# K-Line.net
KiCad netlist of a schematic drawn in Altium Designer
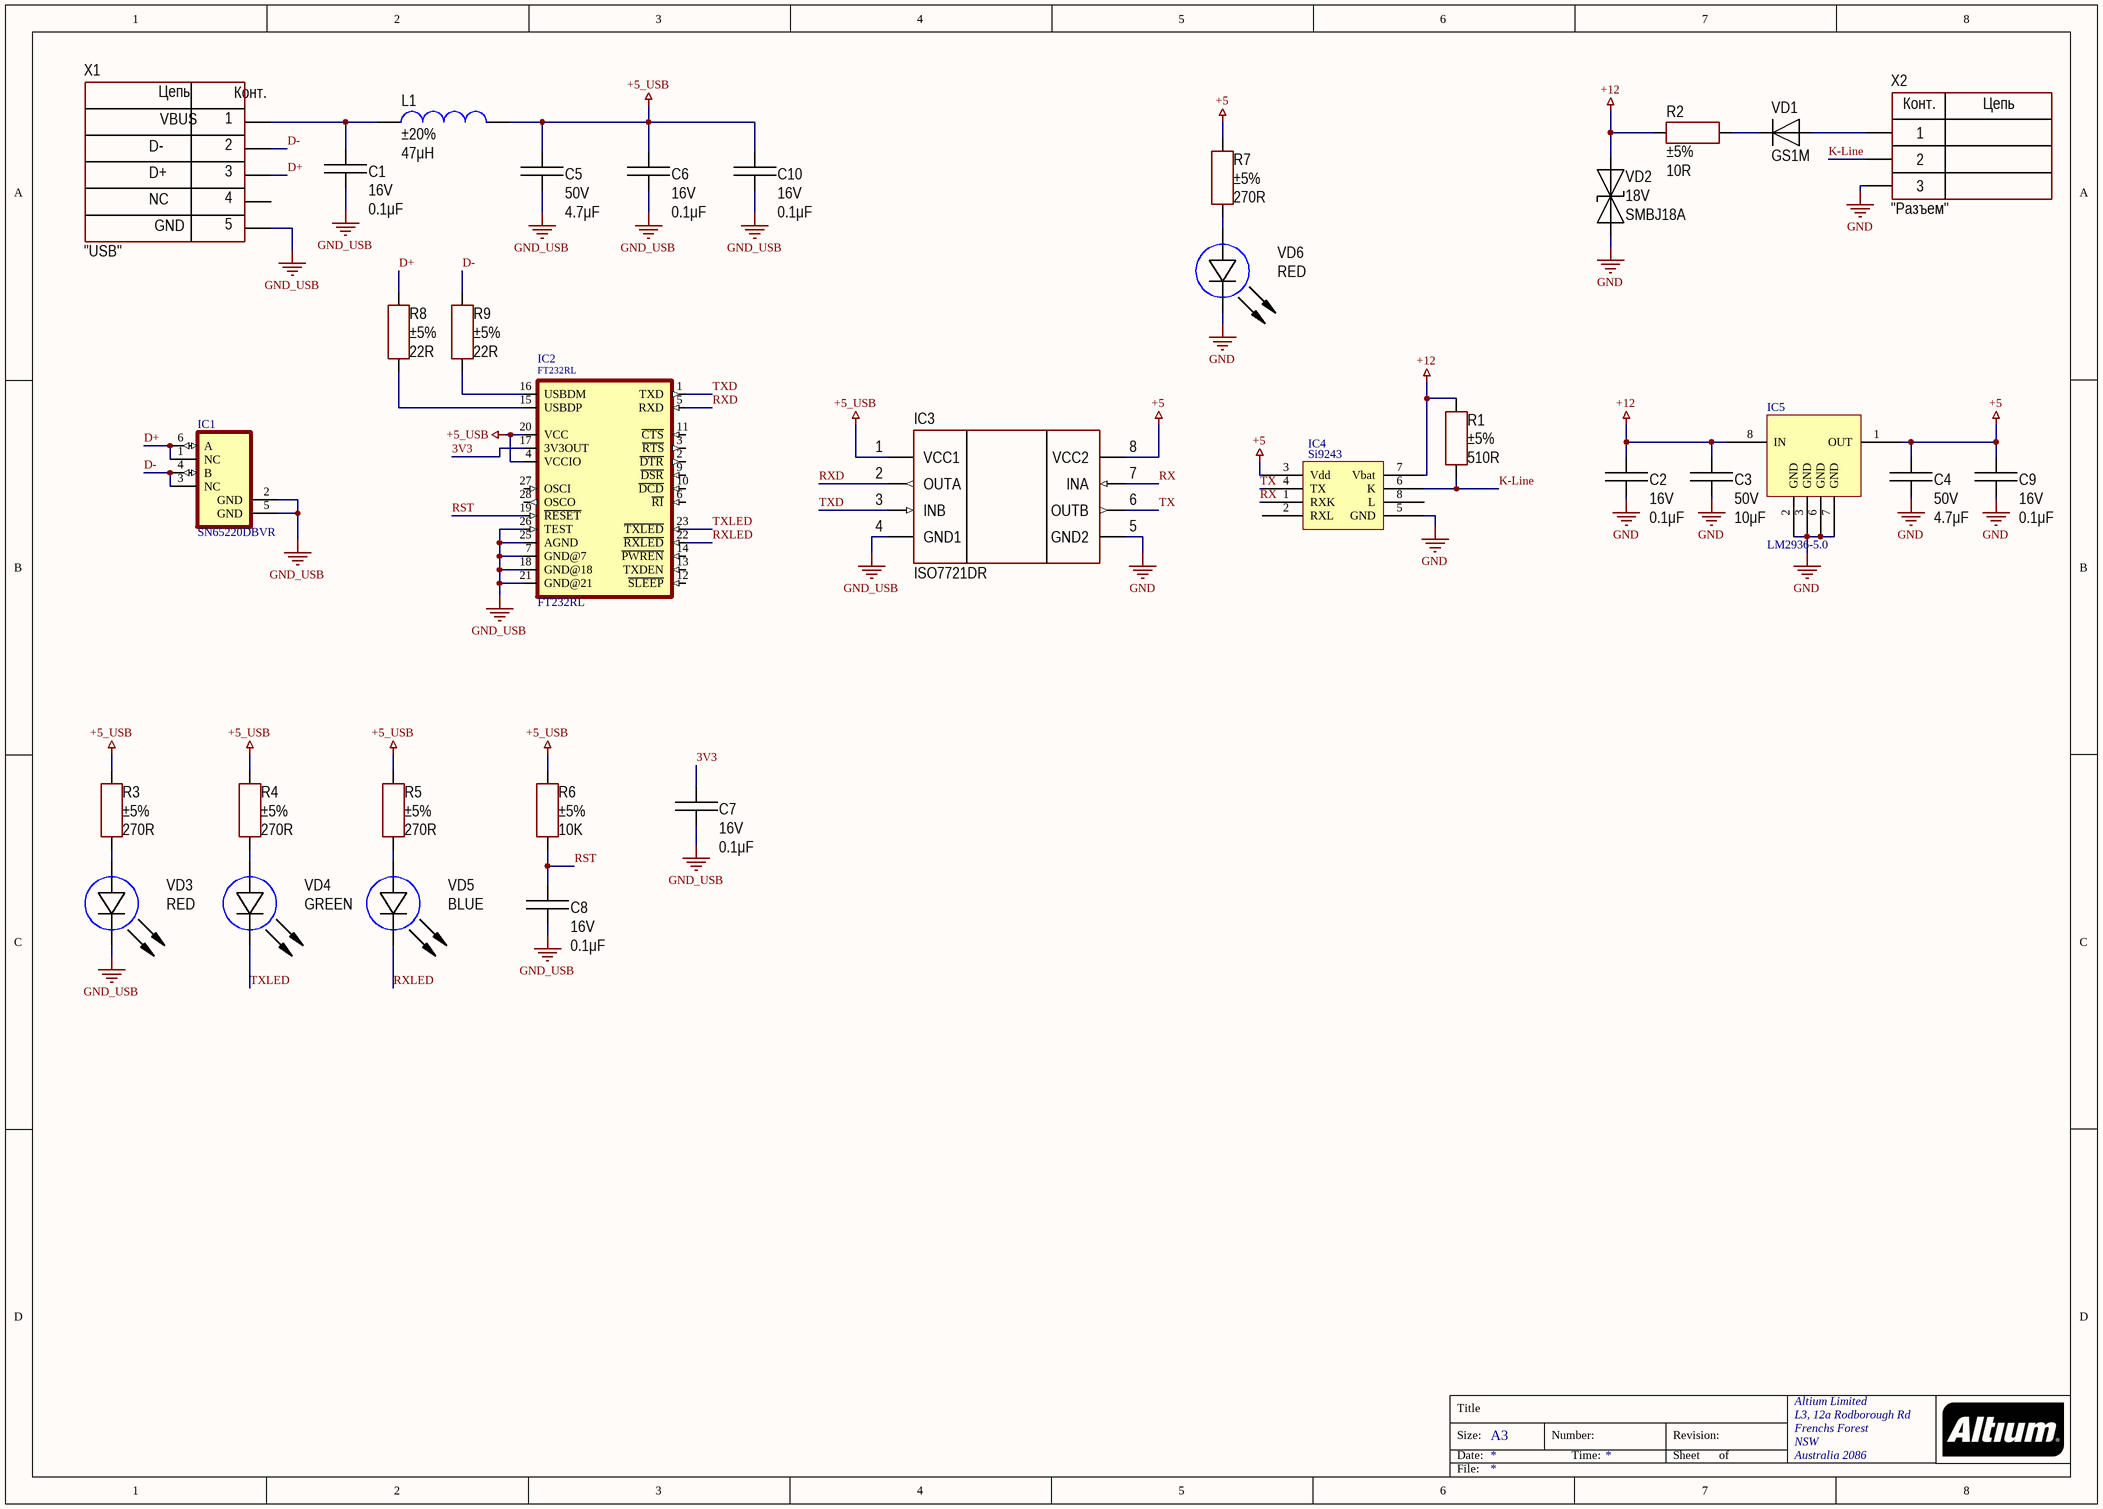
[diagram p0: K-Line.SchDoc]

(export (version "E")
  (design (tool "Eeschema 10.0.6"))
  (components
    (comp (ref "C1")
      (value "0.1μF")
      (footprint "StandardCase:CAP: 0805")
      (fields
        (field (name "MANUFACTURER") "Yageo")
        (field (name "PARTNUMBER") "CC0805KRX7R7BB104")
        (field (name "VALUEMANUFACTURERPARTNUMBER") "Ceramic capacitor, 0.1μF, X7R, ±10%, 16V, 0805, -55...+125°C")
        (field (name "VOLTAGE") "16V")
      )
      (libsource (lib "Capacitor") (part "Ceramic_0805"))
    )
    (comp (ref "C2")
      (value "0.1μF")
      (footprint "StandardCase:CAP: 0805")
      (fields
        (field (name "MANUFACTURER") "Yageo")
        (field (name "PARTNUMBER") "CC0805KRX7R7BB104")
        (field (name "VALUEMANUFACTURERPARTNUMBER") "Ceramic capacitor, 0.1μF, X7R, ±10%, 16V, 0805, -55...+125°C")
        (field (name "VOLTAGE") "16V")
      )
      (libsource (lib "Capacitor") (part "Ceramic_0805"))
    )
    (comp (ref "C3")
      (value "10μF")
      (footprint "StandardCase:CAP: 1210")
      (fields
        (field (name "MANUFACTURER") "Yageo")
        (field (name "PARTNUMBER") "CC1210KKX7R9BB104")
        (field (name "VALUEMANUFACTURERPARTNUMBER") "Ceramic capacitor, 10μF, X7R, ±10%, 50V, 1210, -55...+125°C")
        (field (name "VOLTAGE") "50V")
      )
      (libsource (lib "Capacitor") (part "Ceramic_1210"))
    )
    (comp (ref "C4")
      (value "4.7μF")
      (footprint "StandardCase:CAP: 1206")
      (fields
        (field (name "MANUFACTURER") "Yageo")
        (field (name "PARTNUMBER") "CC1206KRX7R9BB104")
        (field (name "VALUEMANUFACTURERPARTNUMBER") "Ceramic capacitor, 4.7μF, X7R, ±10%, 50V, 1206, -55...+125°C")
        (field (name "VOLTAGE") "50V")
      )
      (libsource (lib "Capacitor") (part "Ceramic_1206"))
    )
    (comp (ref "C5")
      (value "4.7μF")
      (footprint "StandardCase:CAP: 1206")
      (fields
        (field (name "MANUFACTURER") "Yageo")
        (field (name "PARTNUMBER") "CC1206KRX7R9BB104")
        (field (name "VALUEMANUFACTURERPARTNUMBER") "Ceramic capacitor, 4.7μF, X7R, ±10%, 50V, 1206, -55...+125°C")
        (field (name "VOLTAGE") "50V")
      )
      (libsource (lib "Capacitor") (part "Ceramic_1206"))
    )
    (comp (ref "C6")
      (value "0.1μF")
      (footprint "StandardCase:CAP: 0805")
      (fields
        (field (name "MANUFACTURER") "Yageo")
        (field (name "PARTNUMBER") "CC0805KRX7R7BB104")
        (field (name "VALUEMANUFACTURERPARTNUMBER") "Ceramic capacitor, 0.1μF, X7R, ±10%, 16V, 0805, -55...+125°C")
        (field (name "VOLTAGE") "16V")
      )
      (libsource (lib "Capacitor") (part "Ceramic_0805"))
    )
    (comp (ref "C7")
      (value "0.1μF")
      (footprint "StandardCase:CAP: 0603")
      (fields
        (field (name "MANUFACTURER") "Yageo")
        (field (name "PARTNUMBER") "CC0603KRX7R7BB104")
        (field (name "VALUEMANUFACTURERPARTNUMBER") "Ceramic capacitor, 0.1μF, X7R, ±10%, 16V, 0603, -55...+125°C")
        (field (name "VOLTAGE") "16V")
      )
      (libsource (lib "Capacitor") (part "Ceramic_0603"))
    )
    (comp (ref "C8")
      (value "0.1μF")
      (footprint "StandardCase:CAP: 0603")
      (fields
        (field (name "MANUFACTURER") "Yageo")
        (field (name "PARTNUMBER") "CC0603KRX7R7BB104")
        (field (name "VALUEMANUFACTURERPARTNUMBER") "Ceramic capacitor, 0.1μF, X7R, ±10%, 16V, 0603, -55...+125°C")
        (field (name "VOLTAGE") "16V")
      )
      (libsource (lib "Capacitor") (part "Ceramic_0603"))
    )
    (comp (ref "C9")
      (value "0.1μF")
      (footprint "StandardCase:CAP: 0805")
      (fields
        (field (name "MANUFACTURER") "Yageo")
        (field (name "PARTNUMBER") "CC0805KRX7R7BB104")
        (field (name "VALUEMANUFACTURERPARTNUMBER") "Ceramic capacitor, 0.1μF, X7R, ±10%, 16V, 0805, -55...+125°C")
        (field (name "VOLTAGE") "16V")
      )
      (libsource (lib "Capacitor") (part "Ceramic_0805"))
    )
    (comp (ref "C10")
      (value "0.1μF")
      (footprint "StandardCase:CAP: 0603")
      (fields
        (field (name "MANUFACTURER") "Yageo")
        (field (name "PARTNUMBER") "CC0805KRX7R7BB104")
        (field (name "VALUEMANUFACTURERPARTNUMBER") "Ceramic capacitor, 0.1μF, X7R, ±10%, 16V, 0805, -55...+125°C")
        (field (name "VOLTAGE") "16V")
      )
      (libsource (lib "Capacitor") (part "Ceramic_0805"))
    )
    (comp (ref "IC1")
      (value "SN65220DBVR")
      (footprint "StandardCase:SOT23-6")
      (description "IC SINGLE USB PORT TVS SOT-23-6")
      (fields (field (name "MF") "Texas Instruments"))
      (libsource (lib "SN65220DBVR") (part "SN65220DBVR"))
    )
    (comp (ref "IC2")
      (value "FT232RL")
      (footprint "StandardCase:28-SSOP")
      (description "USB ë¸Œë¦¬ì§€, USB-UART USB 2.0 UART ì¸í„°íŽ˜ì´ìŠ¤ 28-SSOP")
      (fields (field (name "MF") "FTDI, Future"))
      (libsource (lib "FT232RL") (part "FT232RL"))
    )
    (comp (ref "IC3")
      (value "~")
      (footprint "StandardCase:8-SOIC")
      (description "Digital isolator")
      (fields
        (field (name "MANUFACTURER") "Texas Instruments")
        (field (name "VALUEMANUFACTURERPARTNUMBER") "IC digital isolator, 100Mbps, 3000Vrms, 2.25...5.5V, -55...+125°C, 8-SOIC")
        (field (name "PARTNUMBER") "ISO7721DR")
      )
      (libsource (lib "IC. Interface") (part "ISO7721DR"))
    )
    (comp (ref "IC4")
      (value "Si9243")
      (footprint "StandardCase:8-SOIC")
      (libsource (lib "Si9243") (part "Si9243"))
    )
    (comp (ref "IC5")
      (value "LM2936-5.0")
      (footprint "StandardCase:8-SOIC")
      (libsource (lib "LM2936-5.0") (part "LM2936-5.0"))
    )
    (comp (ref "L1")
      (value "47μH")
      (footprint "StandardCase:IND: 0805")
      (fields
        (field (name "MANUFACTURER") "Murata Electronics")
        (field (name "PARTNUMBER") "LQM21FN100M70L")
        (field (name "VALUEMANUFACTURERPARTNUMBER") "Fixed inductor, 47μH, ±20%, 0805, 100mA, -55...+125°C")
        (field (name "TOLERANCE") "±20%")
      )
      (libsource (lib "Inductor") (part "Inductor_0805"))
    )
    (comp (ref "R1")
      (value "510R")
      (footprint "StandardCase:RES: 2010")
      (fields
        (field (name "MANUFACTURER") "Yageo")
        (field (name "PARTNUMBER") "RC2010JK-07100RL")
        (field (name "VALUEMANUFACTURERPARTNUMBER") "Resistor film, 510R, ±5%, 2010, 0.75W, -55...+125°C")
        (field (name "TOLERANCE") "±5%")
      )
      (libsource (lib "Resistor") (part "Resistor_2010"))
    )
    (comp (ref "R2")
      (value "10R")
      (footprint "StandardCase:RES: 1206")
      (fields
        (field (name "MANUFACTURER") "Yageo")
        (field (name "PARTNUMBER") "RC1206JR-07100RL")
        (field (name "VALUEMANUFACTURERPARTNUMBER") "Resistor film, 10R, ±5%, 1206, 0.25W, -55...+125°C")
        (field (name "TOLERANCE") "±5%")
      )
      (libsource (lib "Resistor") (part "Resistor_1206"))
    )
    (comp (ref "R3")
      (value "270R")
      (footprint "StandardCase:RES: 0603")
      (fields
        (field (name "MANUFACTURER") "Yageo")
        (field (name "PARTNUMBER") "RC0603JR-07100RL")
        (field (name "VALUEMANUFACTURERPARTNUMBER") "Resistor film, 270R, ±5%, 0603, 0.1W, -55...+125°C")
        (field (name "TOLERANCE") "±5%")
      )
      (libsource (lib "Resistor") (part "Resistor_0603"))
    )
    (comp (ref "R4")
      (value "270R")
      (footprint "StandardCase:RES: 0603")
      (fields
        (field (name "MANUFACTURER") "Yageo")
        (field (name "PARTNUMBER") "RC0603JR-07100RL")
        (field (name "VALUEMANUFACTURERPARTNUMBER") "Resistor film, 270R, ±5%, 0603, 0.1W, -55...+125°C")
        (field (name "TOLERANCE") "±5%")
      )
      (libsource (lib "Resistor") (part "Resistor_0603"))
    )
    (comp (ref "R5")
      (value "270R")
      (footprint "StandardCase:RES: 0603")
      (fields
        (field (name "MANUFACTURER") "Yageo")
        (field (name "PARTNUMBER") "RC0603JR-07100RL")
        (field (name "VALUEMANUFACTURERPARTNUMBER") "Resistor film, 270R, ±5%, 0603, 0.1W, -55...+125°C")
        (field (name "TOLERANCE") "±5%")
      )
      (libsource (lib "Resistor") (part "Resistor_0603"))
    )
    (comp (ref "R6")
      (value "10K")
      (footprint "StandardCase:RES: 0603")
      (fields
        (field (name "MANUFACTURER") "Yageo")
        (field (name "PARTNUMBER") "RC0603JR-07100RL")
        (field (name "VALUEMANUFACTURERPARTNUMBER") "Resistor film, 10K, ±5%, 0603, 0.1W, -55...+125°C")
        (field (name "TOLERANCE") "±5%")
      )
      (libsource (lib "Resistor") (part "Resistor_0603"))
    )
    (comp (ref "R7")
      (value "270R")
      (footprint "StandardCase:RES: 0603")
      (fields
        (field (name "MANUFACTURER") "Yageo")
        (field (name "PARTNUMBER") "RC0603JR-07100RL")
        (field (name "VALUEMANUFACTURERPARTNUMBER") "Resistor film, 270R, ±5%, 0603, 0.1W, -55...+125°C")
        (field (name "TOLERANCE") "±5%")
      )
      (libsource (lib "Resistor") (part "Resistor_0603"))
    )
    (comp (ref "R8")
      (value "22R")
      (footprint "StandardCase:RES: 0603")
      (fields
        (field (name "MANUFACTURER") "Yageo")
        (field (name "PARTNUMBER") "RC0603JR-07100RL")
        (field (name "VALUEMANUFACTURERPARTNUMBER") "Resistor film, 22R, ±5%, 0603, 0.1W, -55...+125°C")
        (field (name "TOLERANCE") "±5%")
      )
      (libsource (lib "Resistor") (part "Resistor_0603"))
    )
    (comp (ref "R9")
      (value "22R")
      (footprint "StandardCase:RES: 0603")
      (fields
        (field (name "MANUFACTURER") "Yageo")
        (field (name "PARTNUMBER") "RC0603JR-07100RL")
        (field (name "VALUEMANUFACTURERPARTNUMBER") "Resistor film, 22R, ±5%, 0603, 0.1W, -55...+125°C")
        (field (name "TOLERANCE") "±5%")
      )
      (libsource (lib "Resistor") (part "Resistor_0603"))
    )
    (comp (ref "VD1")
      (value "~")
      (footprint "StandardCase:DIODE: SMA")
      (fields
        (field (name "MANUFACTURER") "Micro Commercial")
        (field (name "VALUEMANUFACTURERPARTNUMBER") "Single diode, 75V, 150mA, 1V, 4ns, SOD-323, -55...+150°C")
        (field (name "VOLTAGE") "75V")
        (field (name "PARTNUMBER") "GS1M")
      )
      (libsource (lib "Diode") (part "Diode_single"))
    )
    (comp (ref "VD2")
      (value "~")
      (footprint "StandardCase:DIODE: SMB")
      (fields
        (field (name "MANUFACTURER") "Diodes Incorporated")
        (field (name "VALUEMANUFACTURERPARTNUMBER") "Zener diode, 18V, 500mW, 0.9V, 17Ohm, SOD-123, -55...+150°C")
        (field (name "VOLTAGE") "18V")
        (field (name "PARTNUMBER") "SMBJ18A")
      )
      (libsource (lib "Diode") (part "TVS_single"))
    )
    (comp (ref "VD3")
      (value "~")
      (footprint "StandardCase:LED: 0402B")
      (fields
        (field (name "VALUEMANUFACTURERPARTNUMBER") "LED, *, *, *, -55...+150°C")
        (field (name "COLOR") "RED")
      )
      (libsource (lib "Diode") (part "LED_single"))
    )
    (comp (ref "VD4")
      (value "~")
      (footprint "StandardCase:LED: 0402B")
      (fields
        (field (name "VALUEMANUFACTURERPARTNUMBER") "LED, *, *, *, -55...+150°C")
        (field (name "COLOR") "GREEN")
      )
      (libsource (lib "Diode") (part "LED_single"))
    )
    (comp (ref "VD5")
      (value "~")
      (footprint "StandardCase:LED: 0402B")
      (fields
        (field (name "VALUEMANUFACTURERPARTNUMBER") "LED, *, *, *, -55...+150°C")
        (field (name "COLOR") "BLUE")
      )
      (libsource (lib "Diode") (part "LED_single"))
    )
    (comp (ref "VD6")
      (value "~")
      (footprint "StandardCase:LED: 0402B")
      (fields
        (field (name "VALUEMANUFACTURERPARTNUMBER") "LED, *, *, *, -55...+150°C")
        (field (name "COLOR") "RED")
      )
      (libsource (lib "Diode") (part "LED_single"))
    )
    (comp (ref "X1")
      (value "~")
      (footprint "CustomCase:CON: 0675031020")
      (fields
        (field (name "MANUFACTURER") "Molex")
        (field (name "VALUEMANUFACTURERPARTNUMBER") "USB mini B")
        (field (name "PARTNUMBER") "0675031020")
        (field (name "COMMENTTEXT") "\"USB\"")
      )
      (libsource (lib "Connector") (part "Connector_USB_mini_B"))
    )
    (comp (ref "X2")
      (value "~")
      (footprint "CustomCase:CON: DG350-3.5-03P")
      (fields
        (field (name "MANUFACTURER") "Degson")
        (field (name "VALUEMANUFACTURERPARTNUMBER") "Terminal connector, 3pin, 3.5mm, 300VAC, 10A")
        (field (name "PARTNUMBER") "DG350-3.5-03P-14")
        (field (name "COMMENTTEXT") "\"Разъем\"")
      )
      (libsource (lib "Connector") (part "Connector_terminal_3pin"))
    )
  )
  (nets
    (net (code "1") (name "+5") (class "Default")
      (node (ref "C4") (pin "2") (pinfunction "2_2") (pintype "power_in"))
      (node (ref "C9") (pin "2") (pinfunction "2_2") (pintype "power_in"))
      (node (ref "IC3") (pin "8") (pinfunction "VCC2_8") (pintype "passive"))
      (node (ref "IC4") (pin "3") (pinfunction "Vdd_3") (pintype "passive"))
      (node (ref "IC5") (pin "1") (pinfunction "OUT_1") (pintype "passive"))
      (node (ref "R7") (pin "2") (pinfunction "2_2") (pintype "passive"))
    )
    (net (code "2") (name "+5_USB") (class "Default")
      (node (ref "C10") (pin "2") (pinfunction "2_2") (pintype "power_in"))
      (node (ref "C5") (pin "2") (pinfunction "2_2") (pintype "power_in"))
      (node (ref "C6") (pin "2") (pinfunction "2_2") (pintype "power_in"))
      (node (ref "IC2") (pin "20") (pinfunction "VCC_20") (pintype "power_in"))
      (node (ref "IC2") (pin "4") (pinfunction "VCCIO_4") (pintype "power_in"))
      (node (ref "IC3") (pin "1") (pinfunction "VCC1_1") (pintype "passive"))
      (node (ref "L1") (pin "1") (pinfunction "1_1") (pintype "passive"))
      (node (ref "R3") (pin "2") (pinfunction "2_2") (pintype "passive"))
      (node (ref "R4") (pin "2") (pinfunction "2_2") (pintype "passive"))
      (node (ref "R5") (pin "2") (pinfunction "2_2") (pintype "passive"))
      (node (ref "R6") (pin "2") (pinfunction "2_2") (pintype "passive"))
    )
    (net (code "3") (name "+12") (class "Default")
      (node (ref "C2") (pin "2") (pinfunction "2_2") (pintype "power_in"))
      (node (ref "C3") (pin "2") (pinfunction "2_2") (pintype "power_in"))
      (node (ref "IC4") (pin "7") (pinfunction "Vbat_7") (pintype "passive"))
      (node (ref "IC5") (pin "8") (pinfunction "IN_8") (pintype "passive"))
      (node (ref "R1") (pin "2") (pinfunction "2_2") (pintype "passive"))
      (node (ref "R2") (pin "1") (pinfunction "1_1") (pintype "passive"))
      (node (ref "VD2") (pin "2") (pinfunction "C_2") (pintype "passive"))
    )
    (net (code "4") (name "/3V3") (class "Default")
      (node (ref "C7") (pin "2") (pinfunction "2_2") (pintype "power_in"))
      (node (ref "IC2") (pin "17") (pinfunction "3V3OUT_17") (pintype "power_in"))
    )
    (net (code "5") (name "/D+") (class "Default")
      (node (ref "IC1") (pin "1") (pinfunction "NC_1") (pintype "passive"))
      (node (ref "IC1") (pin "6") (pinfunction "A_6") (pintype "bidirectional"))
      (node (ref "R8") (pin "2") (pinfunction "2_2") (pintype "passive"))
      (node (ref "X1") (pin "3") (pinfunction "3_3") (pintype "passive"))
    )
    (net (code "6") (name "/D-") (class "Default")
      (node (ref "IC1") (pin "3") (pinfunction "NC_3") (pintype "passive"))
      (node (ref "IC1") (pin "4") (pinfunction "B_4") (pintype "bidirectional"))
      (node (ref "R9") (pin "2") (pinfunction "2_2") (pintype "passive"))
      (node (ref "X1") (pin "2") (pinfunction "2_2") (pintype "passive"))
    )
    (net (code "7") (name "/K-Line") (class "Default")
      (node (ref "IC4") (pin "6") (pinfunction "K_6") (pintype "passive"))
      (node (ref "R1") (pin "1") (pinfunction "1_1") (pintype "passive"))
      (node (ref "X2") (pin "2") (pinfunction "2_2") (pintype "passive"))
    )
    (net (code "8") (name "/RST") (class "Default")
      (node (ref "C8") (pin "2") (pinfunction "2_2") (pintype "power_in"))
      (node (ref "IC2") (pin "19") (pinfunction "~{RESET}_19") (pintype "input"))
      (node (ref "R6") (pin "1") (pinfunction "1_1") (pintype "passive"))
    )
    (net (code "9") (name "/RX") (class "Default")
      (node (ref "IC3") (pin "7") (pinfunction "INA_7") (pintype "input"))
      (node (ref "IC4") (pin "1") (pinfunction "RXK_1") (pintype "passive"))
    )
    (net (code "10") (name "/RXD") (class "Default")
      (node (ref "IC2") (pin "5") (pinfunction "RXD_5") (pintype "input"))
      (node (ref "IC3") (pin "2") (pinfunction "OUTA_2") (pintype "output"))
    )
    (net (code "11") (name "/RXLED") (class "Default")
      (node (ref "IC2") (pin "22") (pinfunction "~{RXLED}_22") (pintype "input"))
      (node (ref "VD5") (pin "2") (pinfunction "C_2") (pintype "passive"))
    )
    (net (code "12") (name "/TX") (class "Default")
      (node (ref "IC3") (pin "6") (pinfunction "OUTB_6") (pintype "output"))
      (node (ref "IC4") (pin "4") (pinfunction "TX_4") (pintype "passive"))
    )
    (net (code "13") (name "/TXD") (class "Default")
      (node (ref "IC2") (pin "1") (pinfunction "TXD_1") (pintype "output"))
      (node (ref "IC3") (pin "3") (pinfunction "INB_3") (pintype "input"))
    )
    (net (code "14") (name "/TXLED") (class "Default")
      (node (ref "IC2") (pin "23") (pinfunction "~{TXLED}_23") (pintype "input"))
      (node (ref "VD4") (pin "2") (pinfunction "C_2") (pintype "passive"))
    )
    (net (code "15") (name "GND") (class "Default")
      (node (ref "C2") (pin "1") (pinfunction "1_1") (pintype "power_in"))
      (node (ref "C3") (pin "1") (pinfunction "1_1") (pintype "power_in"))
      (node (ref "C4") (pin "1") (pinfunction "1_1") (pintype "power_in"))
      (node (ref "C9") (pin "1") (pinfunction "1_1") (pintype "power_in"))
      (node (ref "IC3") (pin "5") (pinfunction "GND2_5") (pintype "passive"))
      (node (ref "IC4") (pin "5") (pinfunction "GND_5") (pintype "passive"))
      (node (ref "IC5") (pin "2") (pinfunction "GND_2") (pintype "passive"))
      (node (ref "IC5") (pin "3") (pinfunction "GND_3") (pintype "passive"))
      (node (ref "IC5") (pin "6") (pinfunction "GND_6") (pintype "passive"))
      (node (ref "IC5") (pin "7") (pinfunction "GND_7") (pintype "passive"))
      (node (ref "VD2") (pin "1") (pinfunction "A_1") (pintype "passive"))
      (node (ref "VD6") (pin "2") (pinfunction "C_2") (pintype "passive"))
      (node (ref "X2") (pin "3") (pinfunction "3_3") (pintype "power_in"))
    )
    (net (code "16") (name "GND_USB") (class "Default")
      (node (ref "C1") (pin "1") (pinfunction "1_1") (pintype "power_in"))
      (node (ref "C10") (pin "1") (pinfunction "1_1") (pintype "power_in"))
      (node (ref "C5") (pin "1") (pinfunction "1_1") (pintype "power_in"))
      (node (ref "C6") (pin "1") (pinfunction "1_1") (pintype "power_in"))
      (node (ref "C7") (pin "1") (pinfunction "1_1") (pintype "power_in"))
      (node (ref "C8") (pin "1") (pinfunction "1_1") (pintype "power_in"))
      (node (ref "IC1") (pin "2") (pinfunction "GND_2") (pintype "power_in"))
      (node (ref "IC1") (pin "5") (pinfunction "GND_5") (pintype "power_in"))
      (node (ref "IC2") (pin "18") (pinfunction "GND@18_18") (pintype "power_in"))
      (node (ref "IC2") (pin "21") (pinfunction "GND@21_21") (pintype "power_in"))
      (node (ref "IC2") (pin "25") (pinfunction "AGND_25") (pintype "power_in"))
      (node (ref "IC2") (pin "26") (pinfunction "TEST_26") (pintype "input"))
      (node (ref "IC2") (pin "7") (pinfunction "GND@7_7") (pintype "power_in"))
      (node (ref "IC3") (pin "4") (pinfunction "GND1_4") (pintype "passive"))
      (node (ref "VD3") (pin "2") (pinfunction "C_2") (pintype "passive"))
      (node (ref "X1") (pin "5") (pinfunction "5_5") (pintype "passive"))
    )
    (net (code "17") (name "Net-(C1-Pad2)") (class "Default")
      (node (ref "C1") (pin "2") (pinfunction "2_2") (pintype "power_in"))
      (node (ref "L1") (pin "2") (pinfunction "2_2") (pintype "passive"))
      (node (ref "X1") (pin "1") (pintype "passive"))
    )
    (net (code "18") (name "Net-(IC2-USBDM)") (class "Default")
      (node (ref "IC2") (pin "16") (pinfunction "USBDM_16") (pintype "bidirectional"))
      (node (ref "R9") (pin "1") (pinfunction "1_1") (pintype "passive"))
    )
    (net (code "19") (name "Net-(IC2-USBDP)") (class "Default")
      (node (ref "IC2") (pin "15") (pinfunction "USBDP_15") (pintype "bidirectional"))
      (node (ref "R8") (pin "1") (pinfunction "1_1") (pintype "passive"))
    )
    (net (code "20") (name "Net-(R2-Pad2)") (class "Default")
      (node (ref "R2") (pin "2") (pinfunction "2_2") (pintype "passive"))
      (node (ref "VD1") (pin "2") (pinfunction "2_2") (pintype "passive"))
    )
    (net (code "21") (name "Net-(VD1-Pad1)") (class "Default")
      (node (ref "VD1") (pin "1") (pinfunction "1_1") (pintype "passive"))
      (node (ref "X2") (pin "1") (pinfunction "1_1") (pintype "passive"))
    )
    (net (code "22") (name "Net-(VD3-A)") (class "Default")
      (node (ref "R3") (pin "1") (pinfunction "1_1") (pintype "passive"))
      (node (ref "VD3") (pin "1") (pinfunction "A_1") (pintype "passive"))
    )
    (net (code "23") (name "Net-(VD4-A)") (class "Default")
      (node (ref "R4") (pin "1") (pinfunction "1_1") (pintype "passive"))
      (node (ref "VD4") (pin "1") (pinfunction "A_1") (pintype "passive"))
    )
    (net (code "24") (name "Net-(VD5-A)") (class "Default")
      (node (ref "R5") (pin "1") (pinfunction "1_1") (pintype "passive"))
      (node (ref "VD5") (pin "1") (pinfunction "A_1") (pintype "passive"))
    )
    (net (code "25") (name "Net-(VD6-A)") (class "Default")
      (node (ref "R7") (pin "1") (pinfunction "1_1") (pintype "passive"))
      (node (ref "VD6") (pin "1") (pinfunction "A_1") (pintype "passive"))
    )
    (net (code "26") (name "unconnected-(IC2-OSCI-Pad27)") (class "Default")
      (node (ref "IC2") (pin "27") (pinfunction "OSCI_27") (pintype "input"))
    )
    (net (code "27") (name "unconnected-(IC2-OSCO-Pad28)") (class "Default")
      (node (ref "IC2") (pin "28") (pinfunction "OSCO_28") (pintype "output"))
    )
    (net (code "28") (name "unconnected-(IC2-TXDEN-Pad13)") (class "Default")
      (node (ref "IC2") (pin "13") (pinfunction "TXDEN_13") (pintype "input"))
    )
    (net (code "29") (name "unconnected-(IC2-~{CTS}-Pad11)") (class "Default")
      (node (ref "IC2") (pin "11") (pinfunction "~{CTS}_11") (pintype "input"))
    )
    (net (code "30") (name "unconnected-(IC2-~{DCD}-Pad10)") (class "Default")
      (node (ref "IC2") (pin "10") (pinfunction "~{DCD}_10") (pintype "input"))
    )
    (net (code "31") (name "unconnected-(IC2-~{DSR}-Pad9)") (class "Default")
      (node (ref "IC2") (pin "9") (pinfunction "~{DSR}_9") (pintype "input"))
    )
    (net (code "32") (name "unconnected-(IC2-~{DTR}-Pad2)") (class "Default")
      (node (ref "IC2") (pin "2") (pinfunction "~{DTR}_2") (pintype "output"))
    )
    (net (code "33") (name "unconnected-(IC2-~{PWREN}-Pad14)") (class "Default")
      (node (ref "IC2") (pin "14") (pinfunction "~{PWREN}_14") (pintype "input"))
    )
    (net (code "34") (name "unconnected-(IC2-~{RI}-Pad6)") (class "Default")
      (node (ref "IC2") (pin "6") (pinfunction "~{RI}_6") (pintype "input"))
    )
    (net (code "35") (name "unconnected-(IC2-~{RTS}-Pad3)") (class "Default")
      (node (ref "IC2") (pin "3") (pinfunction "~{RTS}_3") (pintype "output"))
    )
    (net (code "36") (name "unconnected-(IC2-~{SLEEP}-Pad12)") (class "Default")
      (node (ref "IC2") (pin "12") (pinfunction "~{SLEEP}_12") (pintype "input"))
    )
    (net (code "37") (name "unconnected-(IC4-L-Pad8)") (class "Default")
      (node (ref "IC4") (pin "8") (pinfunction "L_8") (pintype "passive"))
    )
    (net (code "38") (name "unconnected-(IC4-RXL-Pad2)") (class "Default")
      (node (ref "IC4") (pin "2") (pinfunction "RXL_2") (pintype "passive"))
    )
    (net (code "39") (name "unconnected-(X1-Pad4)") (class "Default")
      (node (ref "X1") (pin "4") (pinfunction "4_4") (pintype "passive"))
    )
  )
)
